# MainSchem.net
KiCad netlist of a schematic drawn in Altium Designer
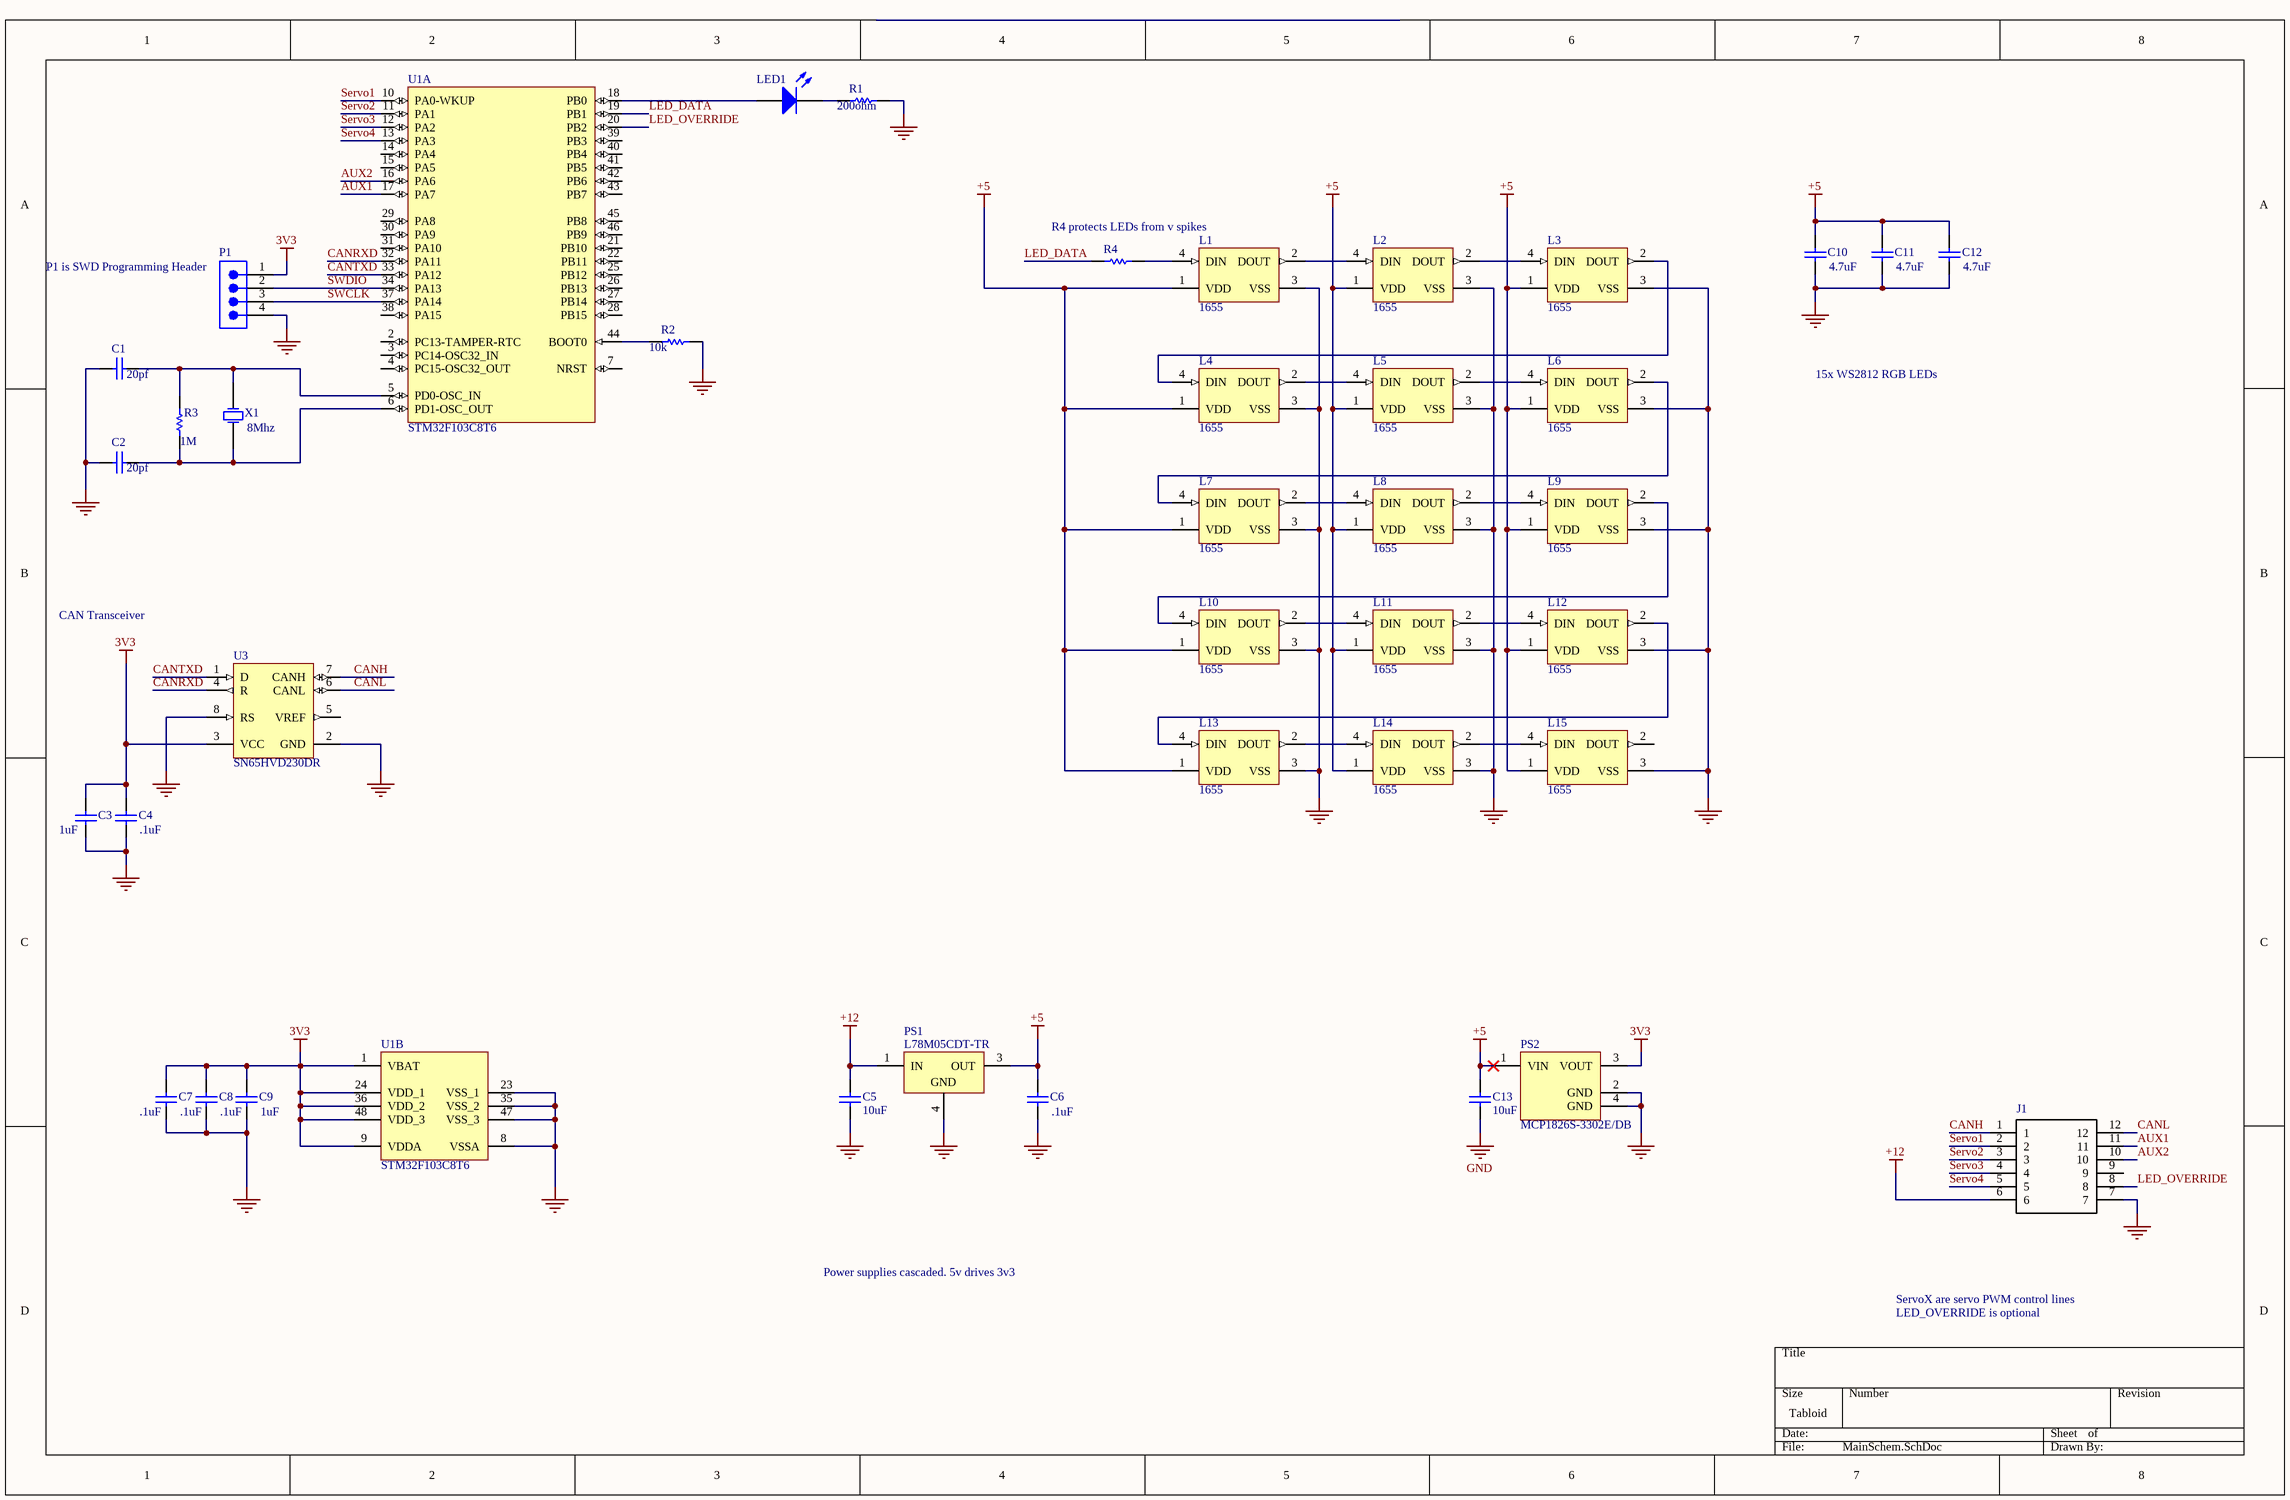
[diagram p0: MainSchem.SchDoc]

(export (version "E")
  (design (tool "Eeschema 10.0.6"))
  (components
    (comp (ref "C1")
      (value "08051A200JAT2A")
      (footprint "CAPC2013X140X50NL20T25")
      (fields (field (name "MANUFACTURER") "AVX Interconnect / Elco"))
      (libsource (lib "Altium Content Vault") (part "CAP"))
    )
    (comp (ref "C2")
      (value "08051A200JAT2A")
      (footprint "CAPC2013X140X50NL20T25")
      (fields (field (name "MANUFACTURER") "AVX Interconnect / Elco"))
      (libsource (lib "Altium Content Vault") (part "CAP"))
    )
    (comp (ref "C3")
      (value "GRM31MR71H105KA88L")
      (footprint "CAPC3216X125X55LL15T25")
      (description "Chip Capacitor, 1 uF, +/- 10%, 50 V, -55 to 125 degC, 1206 (3216 Metric), RoHS, Tape and Reel")
      (fields (field (name "TOLERANCE") "10%") (field (name "MANUFACTURER") "Murata"))
      (libsource (lib "Altium Content Vault") (part "CAP-NP-2"))
    )
    (comp (ref "C4")
      (value "12065C104KAT2A")
      (footprint "CAPC3216X94X50ML20T25")
      (description "Chip Capacitor, Ceramic, 100 nF, 10%, 50 V, 1206, RoHS, Tape and Reel")
      (fields (field (name "MANUFACTURER") "AVX"))
      (libsource (lib "Altium Content Vault") (part "CAP-NP-2"))
    )
    (comp (ref "C5")
      (value "10uF")
      (footprint "MURA-1206_H_1.8_M")
      (description "CAP, Ceramic, 10 uF, 10%, 50 V, 1206, RoHS, Tape and Reel")
      (fields (field (name "TOLERANCE") "10%") (field (name "MANUFACTURER") "Murata"))
      (libsource (lib "Altium Content Vault") (part "CAP-NP-2"))
    )
    (comp (ref "C6")
      (value "12065C104KAT2A")
      (footprint "CAPC3216X94X50ML20T25")
      (description "Chip Capacitor, Ceramic, 100 nF, 10%, 50 V, 1206, RoHS, Tape and Reel")
      (fields (field (name "MANUFACTURER") "AVX"))
      (libsource (lib "Altium Content Vault") (part "CAP-NP-2"))
    )
    (comp (ref "C7")
      (value "12065C104KAT2A")
      (footprint "CAPC3216X94X50ML20T25")
      (description "Chip Capacitor, Ceramic, 100 nF, 10%, 50 V, 1206, RoHS, Tape and Reel")
      (fields (field (name "MANUFACTURER") "AVX"))
      (libsource (lib "Altium Content Vault") (part "CAP-NP-2"))
    )
    (comp (ref "C8")
      (value "12065C104KAT2A")
      (footprint "CAPC3216X94X50ML20T25")
      (description "Chip Capacitor, Ceramic, 100 nF, 10%, 50 V, 1206, RoHS, Tape and Reel")
      (fields (field (name "MANUFACTURER") "AVX"))
      (libsource (lib "Altium Content Vault") (part "CAP-NP-2"))
    )
    (comp (ref "C9")
      (value "12065C104KAT2A")
      (footprint "CAPC3216X94X50ML20T25")
      (description "Chip Capacitor, Ceramic, 100 nF, 10%, 50 V, 1206, RoHS, Tape and Reel")
      (fields (field (name "MANUFACTURER") "AVX"))
      (libsource (lib "Altium Content Vault") (part "CAP-NP-2"))
    )
    (comp (ref "C10")
      (value "CGA6M3X7S2A475K200AB")
      (footprint "CAPC3225X220X20LL40")
      (description "Chip Capacitor, 4.7 uF, +/- 10%, 100 V, -55 to 125 degC, 1210 (3225 Metric), RoHS, Tape and Reel")
      (fields (field (name "TOLERANCE") "10%") (field (name "MANUFACTURER") "TDK"))
      (libsource (lib "Altium Content Vault") (part "CAP-NP-2"))
    )
    (comp (ref "C11")
      (value "CGA6M3X7S2A475K200AB")
      (footprint "CAPC3225X220X20LL40")
      (description "Chip Capacitor, 4.7 uF, +/- 10%, 100 V, -55 to 125 degC, 1210 (3225 Metric), RoHS, Tape and Reel")
      (fields (field (name "TOLERANCE") "10%") (field (name "MANUFACTURER") "TDK"))
      (libsource (lib "Altium Content Vault") (part "CAP-NP-2"))
    )
    (comp (ref "C12")
      (value "CGA6M3X7S2A475K200AB")
      (footprint "CAPC3225X220X20LL40")
      (description "Chip Capacitor, 4.7 uF, +/- 10%, 100 V, -55 to 125 degC, 1210 (3225 Metric), RoHS, Tape and Reel")
      (fields (field (name "TOLERANCE") "10%") (field (name "MANUFACTURER") "TDK"))
      (libsource (lib "Altium Content Vault") (part "CAP-NP-2"))
    )
    (comp (ref "C13")
      (value "10uF")
      (footprint "MURA-1206_H_1.8_M")
      (description "CAP, Ceramic, 10 uF, 10%, 50 V, 1206, RoHS, Tape and Reel")
      (fields (field (name "TOLERANCE") "10%") (field (name "MANUFACTURER") "Murata"))
      (libsource (lib "Altium Content Vault") (part "CAP-NP-2"))
    )
    (comp (ref "J1")
      (value "DTM13-12PA")
      (footprint "*TE_DTM13-12PA")
      (fields (field (name "MF") "TE Connectivity"))
      (libsource (lib "DTM13-12PA") (part "DTM13-12PA"))
    )
    (comp (ref "L1")
      (value "1655")
      (footprint "ADA-RGB-1655_V")
      (fields (field (name "MANUFACTURER") "Adafruit-Industries-LLC"))
      (libsource (lib "Altium Content Vault") (part "ADA-RGB-1655-4"))
    )
    (comp (ref "L2")
      (value "1655")
      (footprint "ADA-RGB-1655_V")
      (fields (field (name "MANUFACTURER") "Adafruit-Industries-LLC"))
      (libsource (lib "Altium Content Vault") (part "ADA-RGB-1655-4"))
    )
    (comp (ref "L3")
      (value "1655")
      (footprint "ADA-RGB-1655_V")
      (fields (field (name "MANUFACTURER") "Adafruit-Industries-LLC"))
      (libsource (lib "Altium Content Vault") (part "ADA-RGB-1655-4"))
    )
    (comp (ref "L4")
      (value "1655")
      (footprint "ADA-RGB-1655_V")
      (fields (field (name "MANUFACTURER") "Adafruit-Industries-LLC"))
      (libsource (lib "Altium Content Vault") (part "ADA-RGB-1655-4"))
    )
    (comp (ref "L5")
      (value "1655")
      (footprint "ADA-RGB-1655_V")
      (fields (field (name "MANUFACTURER") "Adafruit-Industries-LLC"))
      (libsource (lib "Altium Content Vault") (part "ADA-RGB-1655-4"))
    )
    (comp (ref "L6")
      (value "1655")
      (footprint "ADA-RGB-1655_V")
      (fields (field (name "MANUFACTURER") "Adafruit-Industries-LLC"))
      (libsource (lib "Altium Content Vault") (part "ADA-RGB-1655-4"))
    )
    (comp (ref "L7")
      (value "1655")
      (footprint "ADA-RGB-1655_V")
      (fields (field (name "MANUFACTURER") "Adafruit-Industries-LLC"))
      (libsource (lib "Altium Content Vault") (part "ADA-RGB-1655-4"))
    )
    (comp (ref "L8")
      (value "1655")
      (footprint "ADA-RGB-1655_V")
      (fields (field (name "MANUFACTURER") "Adafruit-Industries-LLC"))
      (libsource (lib "Altium Content Vault") (part "ADA-RGB-1655-4"))
    )
    (comp (ref "L9")
      (value "1655")
      (footprint "ADA-RGB-1655_V")
      (fields (field (name "MANUFACTURER") "Adafruit-Industries-LLC"))
      (libsource (lib "Altium Content Vault") (part "ADA-RGB-1655-4"))
    )
    (comp (ref "L10")
      (value "1655")
      (footprint "ADA-RGB-1655_V")
      (fields (field (name "MANUFACTURER") "Adafruit-Industries-LLC"))
      (libsource (lib "Altium Content Vault") (part "ADA-RGB-1655-4"))
    )
    (comp (ref "L11")
      (value "1655")
      (footprint "ADA-RGB-1655_V")
      (fields (field (name "MANUFACTURER") "Adafruit-Industries-LLC"))
      (libsource (lib "Altium Content Vault") (part "ADA-RGB-1655-4"))
    )
    (comp (ref "L12")
      (value "1655")
      (footprint "ADA-RGB-1655_V")
      (fields (field (name "MANUFACTURER") "Adafruit-Industries-LLC"))
      (libsource (lib "Altium Content Vault") (part "ADA-RGB-1655-4"))
    )
    (comp (ref "L13")
      (value "1655")
      (footprint "ADA-RGB-1655_V")
      (fields (field (name "MANUFACTURER") "Adafruit-Industries-LLC"))
      (libsource (lib "Altium Content Vault") (part "ADA-RGB-1655-4"))
    )
    (comp (ref "L14")
      (value "1655")
      (footprint "ADA-RGB-1655_V")
      (fields (field (name "MANUFACTURER") "Adafruit-Industries-LLC"))
      (libsource (lib "Altium Content Vault") (part "ADA-RGB-1655-4"))
    )
    (comp (ref "L15")
      (value "1655")
      (footprint "ADA-RGB-1655_V")
      (fields (field (name "MANUFACTURER") "Adafruit-Industries-LLC"))
      (libsource (lib "Altium Content Vault") (part "ADA-RGB-1655-4"))
    )
    (comp (ref "LED1")
      (value "150120GS75000")
      (footprint "1206_A")
      (description "SMD mono-color Chip LED, WL-SMCW, Green")
      (fields (field (name "MANUFACTURER") "Wuerth Elektronik"))
      (libsource (lib "Altium Content Vault") (part "WE-LED_K1A2-2"))
    )
    (comp (ref "P1")
      (value "TSW-104-08-G-S")
      (footprint "SMTC-TSW-104-08-X-S")
      (description "0.025\" SQ Post Header, Through-hole, Vertical, -55 to 125 degC, 2.54 mm Pitch, 4-Pin, Male, RoHS")
      (fields (field (name "MANUFACTURER") "Samtec"))
      (libsource (lib "Altium Content Vault") (part "SMTC-TSW-104-08-X-S"))
    )
    (comp (ref "PS1")
      (value "L78M05CDT-TR")
      (footprint "TO-252_L")
      (description "Positive Voltage Regulator, 5V, 3-Pin DPAK, Tape and Reel")
      (libsource (lib "Altium Content Vault") (part "PM-REG-L4940-SOT3"))
    )
    (comp (ref "PS2")
      (value "MCP1826S-3302E/DB")
      (footprint "SOT-223-DB3_L")
      (description "1000 mA, Low Voltage, Low Quiescent Current LDO Regulator, 3-Pin SOT-223, Extended Temperature")
      (libsource (lib "Altium Content Vault") (part "PM-LINEREG-MCP1826-IL4"))
    )
    (comp (ref "R1")
      (value "CRCW1206200RFKEA")
      (footprint "RESC3216X60X45ML10T20")
      (fields (field (name "MANUFACTURER") "Vishay Dale"))
      (libsource (lib "Altium Content Vault") (part "RES"))
    )
    (comp (ref "R2")
      (value "CRCW120610K0FKEA")
      (footprint "RESC3216X60X45LL10T20")
      (fields (field (name "MANUFACTURER") "Vishay Dale"))
      (libsource (lib "Altium Content Vault") (part "RES"))
    )
    (comp (ref "R3")
      (value "ERJ-8ENF1004V")
      (footprint "RESC3216X70X50NL05T20")
      (fields (field (name "MANUFACTURER") "Panasonic"))
      (libsource (lib "Altium Content Vault") (part "RES"))
    )
    (comp (ref "R4")
      (value "ERJ8ENF3000V")
      (footprint "RESC3216X70X50NL05T20")
      (fields (field (name "MANUFACTURER") "Panasonic"))
      (libsource (lib "Altium Content Vault") (part "RES"))
    )
    (comp (ref "U1")
      (value "STM32F103C8T6")
      (footprint "STM-LQFP48_L")
      (libsource (lib "Altium Content Vault") (part "MC-ARM-STM32F103X8_B-SQ48"))
    )
    (comp (ref "U3")
      (value "SN65HVD230DR")
      (footprint "D0008A_L")
      (fields (field (name "MANUFACTURER") "Texas Instruments"))
      (libsource (lib "Altium Content Vault") (part "TI-SN65HVD230-SOIC_D-8"))
    )
    (comp (ref "X1")
      (value "ABM3-8.000MHZ-D2Y-T")
      (footprint "ABRA-ABM3-2_V")
      (description "Miniature Ceramic Crystal, 8 MHz, -40 to 85 degC, 2-Pin SMD, RoHS, Tape and Reel")
      (fields (field (name "MANUFACTURER") "ABRACON") (field (name "TOLERANCE") "20PPM"))
      (libsource (lib "Altium Content Vault") (part "XTAL_1-2-2"))
    )
  )
  (nets
    (net (code "1") (name "+5") (class "Default")
      (node (ref "C10") (pin "1") (pinfunction "1_1") (pintype "passive"))
      (node (ref "C11") (pin "1") (pinfunction "1_1") (pintype "passive"))
      (node (ref "C12") (pin "1") (pinfunction "1_1") (pintype "passive"))
      (node (ref "C13") (pin "1") (pinfunction "1_1") (pintype "passive"))
      (node (ref "C6") (pin "1") (pinfunction "1_1") (pintype "passive"))
      (node (ref "L1") (pin "1") (pinfunction "VDD_1") (pintype "power_in"))
      (node (ref "L10") (pin "1") (pinfunction "VDD_1") (pintype "power_in"))
      (node (ref "L11") (pin "1") (pinfunction "VDD_1") (pintype "power_in"))
      (node (ref "L12") (pin "1") (pinfunction "VDD_1") (pintype "power_in"))
      (node (ref "L13") (pin "1") (pinfunction "VDD_1") (pintype "power_in"))
      (node (ref "L14") (pin "1") (pinfunction "VDD_1") (pintype "power_in"))
      (node (ref "L15") (pin "1") (pinfunction "VDD_1") (pintype "power_in"))
      (node (ref "L2") (pin "1") (pinfunction "VDD_1") (pintype "power_in"))
      (node (ref "L3") (pin "1") (pinfunction "VDD_1") (pintype "power_in"))
      (node (ref "L4") (pin "1") (pinfunction "VDD_1") (pintype "power_in"))
      (node (ref "L5") (pin "1") (pinfunction "VDD_1") (pintype "power_in"))
      (node (ref "L6") (pin "1") (pinfunction "VDD_1") (pintype "power_in"))
      (node (ref "L7") (pin "1") (pinfunction "VDD_1") (pintype "power_in"))
      (node (ref "L8") (pin "1") (pinfunction "VDD_1") (pintype "power_in"))
      (node (ref "L9") (pin "1") (pinfunction "VDD_1") (pintype "power_in"))
      (node (ref "PS1") (pin "3") (pinfunction "OUT_3") (pintype "power_in"))
      (node (ref "PS2") (pin "1") (pinfunction "VIN_1") (pintype "power_in"))
    )
    (net (code "2") (name "+12") (class "Default")
      (node (ref "C5") (pin "1") (pinfunction "1_1") (pintype "passive"))
      (node (ref "J1") (pin "6") (pinfunction "6_6") (pintype "passive"))
      (node (ref "PS1") (pin "1") (pinfunction "IN_1") (pintype "power_in"))
    )
    (net (code "3") (name "/AUX1") (class "Default")
      (node (ref "J1") (pin "11") (pinfunction "11_11") (pintype "passive"))
      (node (ref "U1") (pin "17") (pinfunction "PA7_17") (pintype "bidirectional"))
    )
    (net (code "4") (name "/AUX2") (class "Default")
      (node (ref "J1") (pin "10") (pinfunction "10_10") (pintype "passive"))
      (node (ref "U1") (pin "16") (pinfunction "PA6_16") (pintype "bidirectional"))
    )
    (net (code "5") (name "/CANH") (class "Default")
      (node (ref "J1") (pin "1") (pinfunction "1_1") (pintype "passive"))
      (node (ref "U3") (pin "7") (pinfunction "CANH_7") (pintype "bidirectional"))
    )
    (net (code "6") (name "/CANL") (class "Default")
      (node (ref "J1") (pin "12") (pinfunction "12_12") (pintype "passive"))
      (node (ref "U3") (pin "6") (pinfunction "CANL_6") (pintype "bidirectional"))
    )
    (net (code "7") (name "/CANRXD") (class "Default")
      (node (ref "U1") (pin "32") (pinfunction "PA11_32") (pintype "bidirectional"))
      (node (ref "U3") (pin "4") (pinfunction "R_4") (pintype "output"))
    )
    (net (code "8") (name "/CANTXD") (class "Default")
      (node (ref "U1") (pin "33") (pinfunction "PA12_33") (pintype "bidirectional"))
      (node (ref "U3") (pin "1") (pinfunction "D_1") (pintype "input"))
    )
    (net (code "9") (name "/LED_DATA") (class "Default")
      (node (ref "R4") (pin "1") (pinfunction "1_1") (pintype "passive"))
      (node (ref "U1") (pin "19") (pinfunction "PB1_19") (pintype "bidirectional"))
    )
    (net (code "10") (name "/LED_OVERRIDE") (class "Default")
      (node (ref "J1") (pin "8") (pinfunction "8_8") (pintype "passive"))
      (node (ref "U1") (pin "20") (pinfunction "PB2_20") (pintype "bidirectional"))
    )
    (net (code "11") (name "/SWCLK") (class "Default")
      (node (ref "P1") (pin "3") (pinfunction "3_3") (pintype "passive"))
      (node (ref "U1") (pin "37") (pinfunction "PA14_37") (pintype "bidirectional"))
    )
    (net (code "12") (name "/SWDIO") (class "Default")
      (node (ref "P1") (pin "2") (pinfunction "2_2") (pintype "passive"))
      (node (ref "U1") (pin "34") (pinfunction "PA13_34") (pintype "bidirectional"))
    )
    (net (code "13") (name "/Servo1") (class "Default")
      (node (ref "J1") (pin "2") (pinfunction "2_2") (pintype "passive"))
      (node (ref "U1") (pin "10") (pinfunction "PA0-WKUP_10") (pintype "bidirectional"))
    )
    (net (code "14") (name "/Servo2") (class "Default")
      (node (ref "J1") (pin "3") (pinfunction "3_3") (pintype "passive"))
      (node (ref "U1") (pin "11") (pinfunction "PA1_11") (pintype "bidirectional"))
    )
    (net (code "15") (name "/Servo3") (class "Default")
      (node (ref "J1") (pin "4") (pinfunction "4_4") (pintype "passive"))
      (node (ref "U1") (pin "12") (pinfunction "PA2_12") (pintype "bidirectional"))
    )
    (net (code "16") (name "/Servo4") (class "Default")
      (node (ref "J1") (pin "5") (pinfunction "5_5") (pintype "passive"))
      (node (ref "U1") (pin "13") (pinfunction "PA3_13") (pintype "bidirectional"))
    )
    (net (code "17") (name "3V3") (class "Default")
      (node (ref "C3") (pin "1") (pinfunction "1_1") (pintype "passive"))
      (node (ref "C4") (pin "1") (pinfunction "1_1") (pintype "passive"))
      (node (ref "C7") (pin "1") (pinfunction "1_1") (pintype "passive"))
      (node (ref "C8") (pin "1") (pinfunction "1_1") (pintype "passive"))
      (node (ref "C9") (pin "1") (pinfunction "1_1") (pintype "passive"))
      (node (ref "P1") (pin "1") (pinfunction "1_1") (pintype "passive"))
      (node (ref "PS2") (pin "3") (pinfunction "VOUT_3") (pintype "power_in"))
      (node (ref "U1") (pin "1") (pinfunction "VBAT_1") (pintype "power_in"))
      (node (ref "U1") (pin "24") (pinfunction "VDD_1_24") (pintype "power_in"))
      (node (ref "U1") (pin "36") (pinfunction "VDD_2_36") (pintype "power_in"))
      (node (ref "U1") (pin "48") (pinfunction "VDD_3_48") (pintype "power_in"))
      (node (ref "U1") (pin "9") (pinfunction "VDDA_9") (pintype "power_in"))
      (node (ref "U3") (pin "3") (pinfunction "VCC_3") (pintype "power_in"))
    )
    (net (code "18") (name "GND") (class "Default")
      (node (ref "C1") (pin "1") (pinfunction "1_1") (pintype "passive"))
      (node (ref "C10") (pin "2") (pinfunction "2_2") (pintype "passive"))
      (node (ref "C11") (pin "2") (pinfunction "2_2") (pintype "passive"))
      (node (ref "C12") (pin "2") (pinfunction "2_2") (pintype "passive"))
      (node (ref "C13") (pin "2") (pinfunction "2_2") (pintype "passive"))
      (node (ref "C2") (pin "1") (pinfunction "1_1") (pintype "passive"))
      (node (ref "C3") (pin "2") (pinfunction "2_2") (pintype "passive"))
      (node (ref "C4") (pin "2") (pinfunction "2_2") (pintype "passive"))
      (node (ref "C5") (pin "2") (pinfunction "2_2") (pintype "passive"))
      (node (ref "C6") (pin "2") (pinfunction "2_2") (pintype "passive"))
      (node (ref "C7") (pin "2") (pinfunction "2_2") (pintype "passive"))
      (node (ref "C8") (pin "2") (pinfunction "2_2") (pintype "passive"))
      (node (ref "C9") (pin "2") (pinfunction "2_2") (pintype "passive"))
      (node (ref "J1") (pin "7") (pinfunction "7_7") (pintype "passive"))
      (node (ref "L1") (pin "3") (pinfunction "VSS_3") (pintype "power_in"))
      (node (ref "L10") (pin "3") (pinfunction "VSS_3") (pintype "power_in"))
      (node (ref "L11") (pin "3") (pinfunction "VSS_3") (pintype "power_in"))
      (node (ref "L12") (pin "3") (pinfunction "VSS_3") (pintype "power_in"))
      (node (ref "L13") (pin "3") (pinfunction "VSS_3") (pintype "power_in"))
      (node (ref "L14") (pin "3") (pinfunction "VSS_3") (pintype "power_in"))
      (node (ref "L15") (pin "3") (pinfunction "VSS_3") (pintype "power_in"))
      (node (ref "L2") (pin "3") (pinfunction "VSS_3") (pintype "power_in"))
      (node (ref "L3") (pin "3") (pinfunction "VSS_3") (pintype "power_in"))
      (node (ref "L4") (pin "3") (pinfunction "VSS_3") (pintype "power_in"))
      (node (ref "L5") (pin "3") (pinfunction "VSS_3") (pintype "power_in"))
      (node (ref "L6") (pin "3") (pinfunction "VSS_3") (pintype "power_in"))
      (node (ref "L7") (pin "3") (pinfunction "VSS_3") (pintype "power_in"))
      (node (ref "L8") (pin "3") (pinfunction "VSS_3") (pintype "power_in"))
      (node (ref "L9") (pin "3") (pinfunction "VSS_3") (pintype "power_in"))
      (node (ref "P1") (pin "4") (pinfunction "4_4") (pintype "passive"))
      (node (ref "PS1") (pin "4") (pinfunction "GND_4") (pintype "power_in"))
      (node (ref "PS2") (pin "2") (pinfunction "GND_2") (pintype "power_in"))
      (node (ref "PS2") (pin "4") (pinfunction "GND_4") (pintype "power_in"))
      (node (ref "R1") (pin "2") (pinfunction "2_2") (pintype "passive"))
      (node (ref "R2") (pin "2") (pinfunction "2_2") (pintype "passive"))
      (node (ref "U1") (pin "23") (pinfunction "VSS_1_23") (pintype "power_in"))
      (node (ref "U1") (pin "35") (pinfunction "VSS_2_35") (pintype "power_in"))
      (node (ref "U1") (pin "47") (pinfunction "VSS_3_47") (pintype "power_in"))
      (node (ref "U1") (pin "8") (pinfunction "VSSA_8") (pintype "power_in"))
      (node (ref "U3") (pin "2") (pinfunction "GND_2") (pintype "power_in"))
      (node (ref "U3") (pin "8") (pinfunction "RS_8") (pintype "input"))
    )
    (net (code "19") (name "Net-(L1-DIN)") (class "Default")
      (node (ref "L1") (pin "4") (pinfunction "DIN_4") (pintype "input"))
      (node (ref "R4") (pin "2") (pinfunction "2_2") (pintype "passive"))
    )
    (net (code "20") (name "Net-(L1-DOUT)") (class "Default")
      (node (ref "L1") (pin "2") (pinfunction "DOUT_2") (pintype "output"))
      (node (ref "L2") (pin "4") (pinfunction "DIN_4") (pintype "input"))
    )
    (net (code "21") (name "Net-(L2-DOUT)") (class "Default")
      (node (ref "L2") (pin "2") (pinfunction "DOUT_2") (pintype "output"))
      (node (ref "L3") (pin "4") (pinfunction "DIN_4") (pintype "input"))
    )
    (net (code "22") (name "Net-(L3-DOUT)") (class "Default")
      (node (ref "L3") (pin "2") (pinfunction "DOUT_2") (pintype "output"))
      (node (ref "L4") (pin "4") (pinfunction "DIN_4") (pintype "input"))
    )
    (net (code "23") (name "Net-(L4-DOUT)") (class "Default")
      (node (ref "L4") (pin "2") (pinfunction "DOUT_2") (pintype "output"))
      (node (ref "L5") (pin "4") (pinfunction "DIN_4") (pintype "input"))
    )
    (net (code "24") (name "Net-(L5-DOUT)") (class "Default")
      (node (ref "L5") (pin "2") (pinfunction "DOUT_2") (pintype "output"))
      (node (ref "L6") (pin "4") (pinfunction "DIN_4") (pintype "input"))
    )
    (net (code "25") (name "Net-(L6-DOUT)") (class "Default")
      (node (ref "L6") (pin "2") (pinfunction "DOUT_2") (pintype "output"))
      (node (ref "L7") (pin "4") (pinfunction "DIN_4") (pintype "input"))
    )
    (net (code "26") (name "Net-(L7-DOUT)") (class "Default")
      (node (ref "L7") (pin "2") (pinfunction "DOUT_2") (pintype "output"))
      (node (ref "L8") (pin "4") (pinfunction "DIN_4") (pintype "input"))
    )
    (net (code "27") (name "Net-(L8-DOUT)") (class "Default")
      (node (ref "L8") (pin "2") (pinfunction "DOUT_2") (pintype "output"))
      (node (ref "L9") (pin "4") (pinfunction "DIN_4") (pintype "input"))
    )
    (net (code "28") (name "Net-(L10-DIN)") (class "Default")
      (node (ref "L10") (pin "4") (pinfunction "DIN_4") (pintype "input"))
      (node (ref "L9") (pin "2") (pinfunction "DOUT_2") (pintype "output"))
    )
    (net (code "29") (name "Net-(L10-DOUT)") (class "Default")
      (node (ref "L10") (pin "2") (pinfunction "DOUT_2") (pintype "output"))
      (node (ref "L11") (pin "4") (pinfunction "DIN_4") (pintype "input"))
    )
    (net (code "30") (name "Net-(L11-DOUT)") (class "Default")
      (node (ref "L11") (pin "2") (pinfunction "DOUT_2") (pintype "output"))
      (node (ref "L12") (pin "4") (pinfunction "DIN_4") (pintype "input"))
    )
    (net (code "31") (name "Net-(L12-DOUT)") (class "Default")
      (node (ref "L12") (pin "2") (pinfunction "DOUT_2") (pintype "output"))
      (node (ref "L13") (pin "4") (pinfunction "DIN_4") (pintype "input"))
    )
    (net (code "32") (name "Net-(L13-DOUT)") (class "Default")
      (node (ref "L13") (pin "2") (pinfunction "DOUT_2") (pintype "output"))
      (node (ref "L14") (pin "4") (pinfunction "DIN_4") (pintype "input"))
    )
    (net (code "33") (name "Net-(L14-DOUT)") (class "Default")
      (node (ref "L14") (pin "2") (pinfunction "DOUT_2") (pintype "output"))
      (node (ref "L15") (pin "4") (pinfunction "DIN_4") (pintype "input"))
    )
    (net (code "34") (name "Net-(LED1-A)") (class "Default")
      (node (ref "LED1") (pin "2") (pinfunction "A_2") (pintype "passive"))
      (node (ref "U1") (pin "18") (pinfunction "PB0_18") (pintype "bidirectional"))
    )
    (net (code "35") (name "Net-(LED1-K)") (class "Default")
      (node (ref "LED1") (pin "1") (pinfunction "K_1") (pintype "passive"))
      (node (ref "R1") (pin "1") (pinfunction "1_1") (pintype "passive"))
    )
    (net (code "36") (name "Net-(U1A-BOOT0)") (class "Default")
      (node (ref "R2") (pin "1") (pinfunction "1_1") (pintype "passive"))
      (node (ref "U1") (pin "44") (pinfunction "BOOT0_44") (pintype "input"))
    )
    (net (code "37") (name "Net-(U1A-PD0-OSC_IN)") (class "Default")
      (node (ref "C1") (pin "2") (pinfunction "2_2") (pintype "passive"))
      (node (ref "R3") (pin "1") (pinfunction "1_1") (pintype "passive"))
      (node (ref "U1") (pin "5") (pinfunction "PD0-OSC_IN_5") (pintype "bidirectional"))
      (node (ref "X1") (pin "1") (pinfunction "X1_1") (pintype "passive"))
    )
    (net (code "38") (name "Net-(U1A-PD1-OSC_OUT)") (class "Default")
      (node (ref "C2") (pin "2") (pinfunction "2_2") (pintype "passive"))
      (node (ref "R3") (pin "2") (pinfunction "2_2") (pintype "passive"))
      (node (ref "U1") (pin "6") (pinfunction "PD1-OSC_OUT_6") (pintype "bidirectional"))
      (node (ref "X1") (pin "2") (pinfunction "X2_2") (pintype "passive"))
    )
    (net (code "39") (name "unconnected-(J1-Pad9)") (class "Default")
      (node (ref "J1") (pin "9") (pinfunction "9_9") (pintype "passive"))
    )
    (net (code "40") (name "unconnected-(L15-DOUT-Pad2)") (class "Default")
      (node (ref "L15") (pin "2") (pinfunction "DOUT_2") (pintype "output"))
    )
    (net (code "41") (name "unconnected-(U1A-NRST-Pad7)") (class "Default")
      (node (ref "U1") (pin "7") (pinfunction "NRST_7") (pintype "bidirectional"))
    )
    (net (code "42") (name "unconnected-(U1A-PA4-Pad14)") (class "Default")
      (node (ref "U1") (pin "14") (pinfunction "PA4_14") (pintype "bidirectional"))
    )
    (net (code "43") (name "unconnected-(U1A-PA5-Pad15)") (class "Default")
      (node (ref "U1") (pin "15") (pinfunction "PA5_15") (pintype "bidirectional"))
    )
    (net (code "44") (name "unconnected-(U1A-PA8-Pad29)") (class "Default")
      (node (ref "U1") (pin "29") (pinfunction "PA8_29") (pintype "bidirectional"))
    )
    (net (code "45") (name "unconnected-(U1A-PA9-Pad30)") (class "Default")
      (node (ref "U1") (pin "30") (pinfunction "PA9_30") (pintype "bidirectional"))
    )
    (net (code "46") (name "unconnected-(U1A-PA10-Pad31)") (class "Default")
      (node (ref "U1") (pin "31") (pinfunction "PA10_31") (pintype "bidirectional"))
    )
    (net (code "47") (name "unconnected-(U1A-PA15-Pad38)") (class "Default")
      (node (ref "U1") (pin "38") (pinfunction "PA15_38") (pintype "bidirectional"))
    )
    (net (code "48") (name "unconnected-(U1A-PB3-Pad39)") (class "Default")
      (node (ref "U1") (pin "39") (pinfunction "PB3_39") (pintype "bidirectional"))
    )
    (net (code "49") (name "unconnected-(U1A-PB4-Pad40)") (class "Default")
      (node (ref "U1") (pin "40") (pinfunction "PB4_40") (pintype "bidirectional"))
    )
    (net (code "50") (name "unconnected-(U1A-PB5-Pad41)") (class "Default")
      (node (ref "U1") (pin "41") (pinfunction "PB5_41") (pintype "bidirectional"))
    )
    (net (code "51") (name "unconnected-(U1A-PB6-Pad42)") (class "Default")
      (node (ref "U1") (pin "42") (pinfunction "PB6_42") (pintype "bidirectional"))
    )
    (net (code "52") (name "unconnected-(U1A-PB7-Pad43)") (class "Default")
      (node (ref "U1") (pin "43") (pinfunction "PB7_43") (pintype "bidirectional"))
    )
    (net (code "53") (name "unconnected-(U1A-PB8-Pad45)") (class "Default")
      (node (ref "U1") (pin "45") (pinfunction "PB8_45") (pintype "bidirectional"))
    )
    (net (code "54") (name "unconnected-(U1A-PB9-Pad46)") (class "Default")
      (node (ref "U1") (pin "46") (pinfunction "PB9_46") (pintype "bidirectional"))
    )
    (net (code "55") (name "unconnected-(U1A-PB10-Pad21)") (class "Default")
      (node (ref "U1") (pin "21") (pinfunction "PB10_21") (pintype "bidirectional"))
    )
    (net (code "56") (name "unconnected-(U1A-PB11-Pad22)") (class "Default")
      (node (ref "U1") (pin "22") (pinfunction "PB11_22") (pintype "bidirectional"))
    )
    (net (code "57") (name "unconnected-(U1A-PB12-Pad25)") (class "Default")
      (node (ref "U1") (pin "25") (pinfunction "PB12_25") (pintype "bidirectional"))
    )
    (net (code "58") (name "unconnected-(U1A-PB13-Pad26)") (class "Default")
      (node (ref "U1") (pin "26") (pinfunction "PB13_26") (pintype "bidirectional"))
    )
    (net (code "59") (name "unconnected-(U1A-PB14-Pad27)") (class "Default")
      (node (ref "U1") (pin "27") (pinfunction "PB14_27") (pintype "bidirectional"))
    )
    (net (code "60") (name "unconnected-(U1A-PB15-Pad28)") (class "Default")
      (node (ref "U1") (pin "28") (pinfunction "PB15_28") (pintype "bidirectional"))
    )
    (net (code "61") (name "unconnected-(U1A-PC13-TAMPER-RTC-Pad2)") (class "Default")
      (node (ref "U1") (pin "2") (pinfunction "PC13-TAMPER-RTC_2") (pintype "bidirectional"))
    )
    (net (code "62") (name "unconnected-(U1A-PC14-OSC32_IN-Pad3)") (class "Default")
      (node (ref "U1") (pin "3") (pinfunction "PC14-OSC32_IN_3") (pintype "bidirectional"))
    )
    (net (code "63") (name "unconnected-(U1A-PC15-OSC32_OUT-Pad4)") (class "Default")
      (node (ref "U1") (pin "4") (pinfunction "PC15-OSC32_OUT_4") (pintype "bidirectional"))
    )
    (net (code "64") (name "unconnected-(U3-VREF-Pad5)") (class "Default")
      (node (ref "U3") (pin "5") (pinfunction "VREF_5") (pintype "output"))
    )
  )
)
